# Rail_Protection_BP.net
KiCad netlist of a schematic drawn in Altium Designer
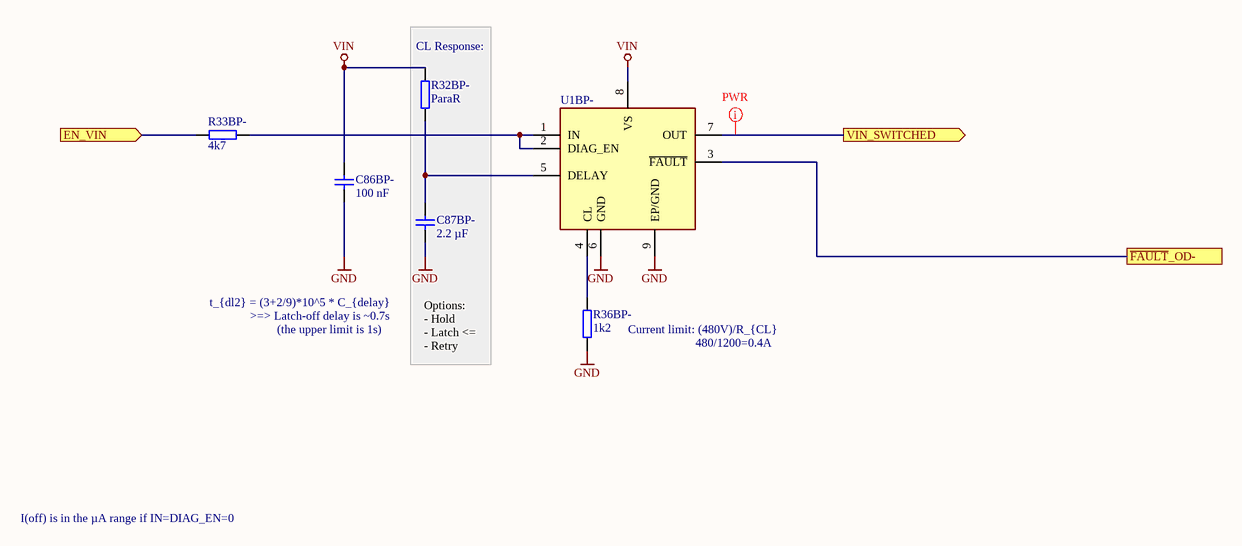
[diagram p0: Rail_Protection_BP.SchDoc]

(export (version "E")
  (design (tool "Eeschema 10.0.6"))
  (components
    (comp (ref "C86BP-")
      (value "100 nF")
      (footprint "C_0603_TE")
      (description "Generic capacitor")
      (fields
        (field (name "MANUFACTURER PART NUMBER") "UZgen_C_0603_100nF_50V_X7R")
        (field (name "MANUFACTURER") "UZgen")
        (field (name "CREATED FROM") "AGeiger")
      )
      (libsource (lib "user") (part "CAP-NP"))
    )
    (comp (ref "C87BP-")
      (value "2.2 µF")
      (footprint "C_0603_TE")
      (description "Generic capacitor")
      (fields
        (field (name "MANUFACTURER PART NUMBER") "UZgen_C_0603_2.2uF_50V_X7R")
        (field (name "MANUFACTURER") "UZgen")
        (field (name "CREATED FROM") "UZgenTool")
      )
      (libsource (lib "user") (part "CAP-NP"))
    )
    (comp (ref "R32BP-")
      (value "ParaR")
      (footprint "R_0603_TE")
      (description "Generic resistor (parametric)")
      (fields
        (field (name "MANUFACTURER PART NUMBER") "UZgen_R_0603_ParaR")
        (field (name "MANUFACTURER") "UZgen")
        (field (name "CREATED FROM") "UZgenTool")
      )
      (libsource (lib "user") (part "RES"))
    )
    (comp (ref "R33BP-")
      (value "4k7")
      (footprint "R_0603_TE")
      (description "Generic resistor")
      (fields
        (field (name "MANUFACTURER PART NUMBER") "UZgen_R_0603_4k7")
        (field (name "MANUFACTURER") "UZgen")
        (field (name "CREATED FROM") "UZgenTool")
      )
      (libsource (lib "user") (part "RES"))
    )
    (comp (ref "R36BP-")
      (value "1k2")
      (footprint "R_0603_TE")
      (description "Generic resistor")
      (fields
        (field (name "MANUFACTURER PART NUMBER") "UZgen_R_0603_1k2")
        (field (name "MANUFACTURER") "UZgen")
        (field (name "CREATED FROM") "UZgenTool")
      )
      (libsource (lib "user") (part "RES"))
    )
    (comp (ref "U1BP-")
      (value "TPS1H000AQDGNRQ1")
      (footprint "SOP65P490X110-9N")
      (fields
        (field (name "MANUFACTURER") "Texas Instruments")
        (field (name "LCSC PART NUMBER") "C2653764")
        (field (name "CREATED FROM") "FRosner")
      )
      (libsource (lib "user") (part "TPS1H000AQDGNRQ1"))
    )
  )
  (nets
    (net (code "1") (name "/EN_VIN") (class "Default")
      (node (ref "R33BP-") (pin "1") (pinfunction "1_1") (pintype "passive"))
    )
    (net (code "2") (name "/VIN_SWITCHED") (class "Default")
      (node (ref "U1BP-") (pin "7") (pinfunction "OUT_7") (pintype "passive"))
    )
    (net (code "3") (name "/~{FAULT}_OD-") (class "Default")
      (node (ref "U1BP-") (pin "3") (pinfunction "~{FAULT}_3") (pintype "open_collector"))
    )
    (net (code "4") (name "GND") (class "Default")
      (node (ref "C86BP-") (pin "1") (pinfunction "1_1") (pintype "passive"))
      (node (ref "C87BP-") (pin "1") (pinfunction "1_1") (pintype "passive"))
      (node (ref "R36BP-") (pin "1") (pinfunction "1_1") (pintype "passive"))
      (node (ref "U1BP-") (pin "6") (pinfunction "GND_6") (pintype "passive"))
      (node (ref "U1BP-") (pin "9") (pinfunction "EP/GND_9") (pintype "passive"))
    )
    (net (code "5") (name "Net-(U1BP--CL)") (class "Default")
      (node (ref "R36BP-") (pin "2") (pinfunction "2_2") (pintype "passive"))
      (node (ref "U1BP-") (pin "4") (pinfunction "CL_4") (pintype "passive"))
    )
    (net (code "6") (name "Net-(U1BP--DELAY)") (class "Default")
      (node (ref "C87BP-") (pin "2") (pinfunction "2_2") (pintype "passive"))
      (node (ref "R32BP-") (pin "1") (pinfunction "1_1") (pintype "passive"))
      (node (ref "U1BP-") (pin "5") (pinfunction "DELAY_5") (pintype "passive"))
    )
    (net (code "7") (name "Net-(U1BP--DIAG_EN)") (class "Default")
      (node (ref "R33BP-") (pin "2") (pinfunction "2_2") (pintype "passive"))
      (node (ref "U1BP-") (pin "1") (pinfunction "IN_1") (pintype "passive"))
      (node (ref "U1BP-") (pin "2") (pinfunction "DIAG_EN_2") (pintype "passive"))
    )
    (net (code "8") (name "VIN") (class "Default")
      (node (ref "C86BP-") (pin "2") (pinfunction "2_2") (pintype "passive"))
      (node (ref "R32BP-") (pin "2") (pinfunction "2_2") (pintype "passive"))
      (node (ref "U1BP-") (pin "8") (pinfunction "VS_8") (pintype "passive"))
    )
  )
)
